# project_1_1.net
KiCad netlist of a schematic drawn in Altium Designer
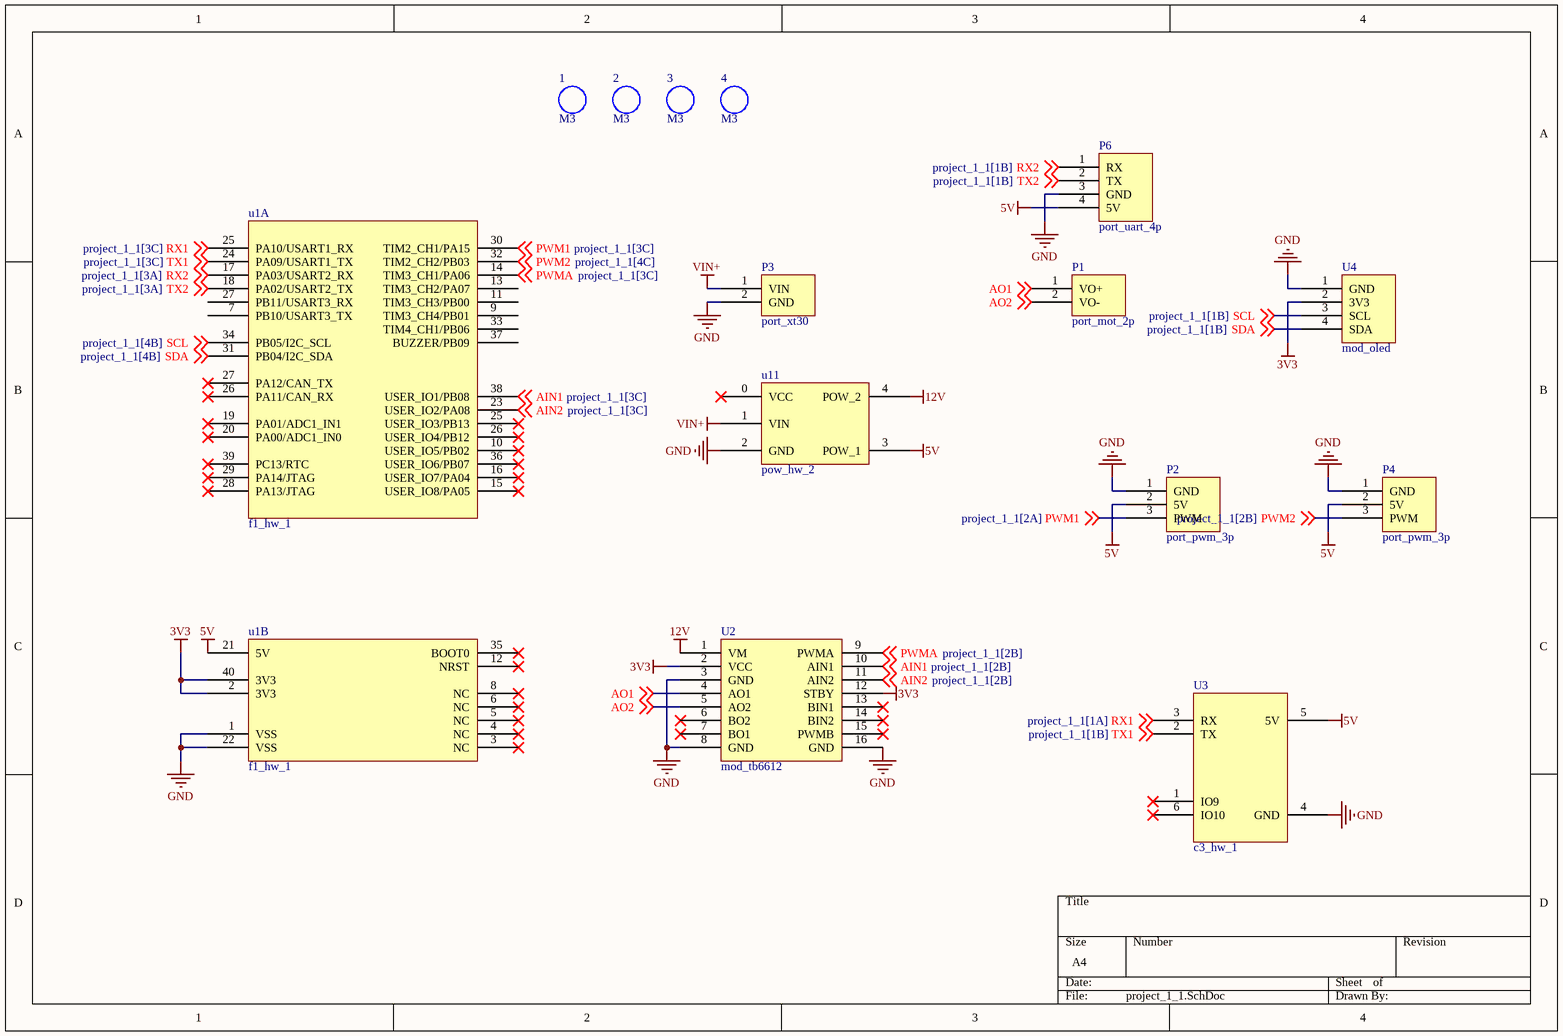
[diagram p0: project_1_1.SchDoc]

(export (version "E")
  (design (tool "Eeschema 10.0.6"))
  (components
    (comp (ref "1")
      (value "M3")
      (footprint "M3 125X200")
      (description "m3铜柱孔")
      (fields (field (name "版权归属") "源创客"))
      (libsource (lib "userLib") (part "prot_m3"))
    )
    (comp (ref "2")
      (value "M3")
      (footprint "M3 125X200")
      (description "m3铜柱孔")
      (fields (field (name "版权归属") "源创客"))
      (libsource (lib "userLib") (part "prot_m3"))
    )
    (comp (ref "3")
      (value "M3")
      (footprint "M3 125X200")
      (description "m3铜柱孔")
      (fields (field (name "版权归属") "源创客"))
      (libsource (lib "userLib") (part "prot_m3"))
    )
    (comp (ref "4")
      (value "M3")
      (footprint "M3 125X200")
      (description "m3铜柱孔")
      (fields (field (name "版权归属") "源创客"))
      (libsource (lib "userLib") (part "prot_m3"))
    )
    (comp (ref "P1")
      (value "port_mot_2p")
      (footprint "XH2.54_2P")
      (description "开环直流电机接口\r\nXH2.54弯排针2p")
      (libsource (lib "userLib") (part "port_mot_2p"))
    )
    (comp (ref "P2")
      (value "port_pwm_3p")
      (footprint "XH2.54_3P")
      (description "舵机接口\r\nXH2.54弯排针3p")
      (libsource (lib "userLib") (part "port_pwm_3p"))
    )
    (comp (ref "P3")
      (value "port_xt30")
      (footprint "MOD_XT30")
      (description "XT30")
      (libsource (lib "userLib") (part "port_xt30"))
    )
    (comp (ref "P4")
      (value "port_pwm_3p")
      (footprint "XH2.54_3P")
      (description "舵机接口\r\nXH2.54弯排针3p")
      (libsource (lib "userLib") (part "port_pwm_3p"))
    )
    (comp (ref "P6")
      (value "port_uart_4p")
      (footprint "XH2.54_4P")
      (description "串口接口/SPP蓝牙模块\r\nXH2.54弯排针4p/4p排母")
      (libsource (lib "userLib") (part "port_uart_4p"))
    )
    (comp (ref "u1")
      (value "f1_hw_1")
      (footprint "f1_hw_1")
      (description "F103C8T6最小系统_1")
      (libsource (lib "userLib") (part "f1_hw_1"))
    )
    (comp (ref "U2")
      (value "mod_tb6612")
      (footprint "MOD_TB6612")
      (description "TB6612模块\r\n8p排母*2")
      (libsource (lib "userLib") (part "mod_tb6612"))
    )
    (comp (ref "U3")
      (value "c3_hw_1")
      (footprint "C3_HW_1")
      (description "ESP32C3蓝牙模块\r\n6p排母")
      (libsource (lib "userLib") (part "c3_hw_1"))
    )
    (comp (ref "U4")
      (value "mod_oled")
      (footprint "mod_oled")
      (description "外购屏幕模块")
      (libsource (lib "userLib") (part "mod_oled"))
    )
    (comp (ref "u11")
      (value "pow_hw_2")
      (footprint "pow_hw_2")
      (description "两路升降压电源模块\r\n6p排母*2")
      (libsource (lib "userLib") (part "pow_hw_2"))
    )
  )
  (nets
    (net (code "1") (name "3V3") (class "Default")
      (node (ref "U2") (pin "12") (pinfunction "STBY_12") (pintype "passive"))
      (node (ref "U2") (pin "2") (pinfunction "VCC_2") (pintype "passive"))
      (node (ref "U4") (pin "2") (pinfunction "3V3_2") (pintype "passive"))
      (node (ref "u1") (pin "2") (pinfunction "3V3_2") (pintype "passive"))
      (node (ref "u1") (pin "40") (pinfunction "3V3_40") (pintype "passive"))
    )
    (net (code "2") (name "5V") (class "Default")
      (node (ref "P2") (pin "2") (pinfunction "5V_2") (pintype "passive"))
      (node (ref "P4") (pin "2") (pinfunction "5V_2") (pintype "passive"))
      (node (ref "P6") (pin "4") (pinfunction "5V_4") (pintype "passive"))
      (node (ref "U3") (pin "5") (pinfunction "5V_5") (pintype "passive"))
      (node (ref "u1") (pin "21") (pinfunction "5V_21") (pintype "passive"))
      (node (ref "u11") (pin "3") (pinfunction "POW_1_3") (pintype "passive"))
    )
    (net (code "3") (name "12V") (class "Default")
      (node (ref "U2") (pin "1") (pinfunction "VM_1") (pintype "passive"))
      (node (ref "u11") (pin "4") (pinfunction "POW_2_4") (pintype "passive"))
    )
    (net (code "4") (name "AIN1") (class "Default")
      (node (ref "U2") (pin "10") (pinfunction "AIN1_10") (pintype "passive"))
      (node (ref "u1") (pin "38") (pinfunction "USER_IO1/PB08_38") (pintype "passive"))
    )
    (net (code "5") (name "AIN2") (class "Default")
      (node (ref "U2") (pin "11") (pinfunction "AIN2_11") (pintype "passive"))
      (node (ref "u1") (pin "23") (pinfunction "USER_IO2/PA08_23") (pintype "passive"))
    )
    (net (code "6") (name "AO1") (class "Default")
      (node (ref "P1") (pin "1") (pinfunction "VO+_1") (pintype "passive"))
      (node (ref "U2") (pin "4") (pinfunction "AO1_4") (pintype "passive"))
    )
    (net (code "7") (name "AO2") (class "Default")
      (node (ref "P1") (pin "2") (pinfunction "VO-_2") (pintype "passive"))
      (node (ref "U2") (pin "5") (pinfunction "AO2_5") (pintype "passive"))
    )
    (net (code "8") (name "GND") (class "Default")
      (node (ref "P2") (pin "1") (pinfunction "GND_1") (pintype "passive"))
      (node (ref "P3") (pin "2") (pinfunction "GND_2") (pintype "passive"))
      (node (ref "P4") (pin "1") (pinfunction "GND_1") (pintype "passive"))
      (node (ref "P6") (pin "3") (pinfunction "GND_3") (pintype "passive"))
      (node (ref "U2") (pin "16") (pinfunction "GND_16") (pintype "passive"))
      (node (ref "U2") (pin "3") (pinfunction "GND_3") (pintype "passive"))
      (node (ref "U2") (pin "8") (pinfunction "GND_8") (pintype "passive"))
      (node (ref "U3") (pin "4") (pinfunction "GND_4") (pintype "passive"))
      (node (ref "U4") (pin "1") (pinfunction "GND_1") (pintype "passive"))
      (node (ref "u1") (pin "1") (pinfunction "VSS_1") (pintype "passive"))
      (node (ref "u1") (pin "22") (pinfunction "VSS_22") (pintype "passive"))
      (node (ref "u11") (pin "2") (pinfunction "GND_2") (pintype "passive"))
    )
    (net (code "9") (name "PWM1") (class "Default")
      (node (ref "P2") (pin "3") (pinfunction "PWM_3") (pintype "passive"))
      (node (ref "u1") (pin "30") (pinfunction "TIM2_CH1/PA15_30") (pintype "passive"))
    )
    (net (code "10") (name "PWM2") (class "Default")
      (node (ref "P4") (pin "3") (pinfunction "PWM_3") (pintype "passive"))
      (node (ref "u1") (pin "32") (pinfunction "TIM2_CH2/PB03_32") (pintype "passive"))
    )
    (net (code "11") (name "PWMA") (class "Default")
      (node (ref "U2") (pin "9") (pinfunction "PWMA_9") (pintype "passive"))
      (node (ref "u1") (pin "14") (pinfunction "TIM3_CH1/PA06_14") (pintype "passive"))
    )
    (net (code "12") (name "RX1") (class "Default")
      (node (ref "U3") (pin "3") (pinfunction "RX_3") (pintype "passive"))
      (node (ref "u1") (pin "25") (pinfunction "PA10/USART1_RX_25") (pintype "passive"))
    )
    (net (code "13") (name "RX2") (class "Default")
      (node (ref "P6") (pin "1") (pinfunction "RX_1") (pintype "passive"))
      (node (ref "u1") (pin "17") (pinfunction "PA03/USART2_RX_17") (pintype "passive"))
    )
    (net (code "14") (name "SCL") (class "Default")
      (node (ref "U4") (pin "3") (pinfunction "SCL_3") (pintype "passive"))
      (node (ref "u1") (pin "34") (pinfunction "PB05/I2C_SCL_34") (pintype "passive"))
    )
    (net (code "15") (name "SDA") (class "Default")
      (node (ref "U4") (pin "4") (pinfunction "SDA_4") (pintype "passive"))
      (node (ref "u1") (pin "31") (pinfunction "PB04/I2C_SDA_31") (pintype "passive"))
    )
    (net (code "16") (name "TX1") (class "Default")
      (node (ref "U3") (pin "2") (pinfunction "TX_2") (pintype "passive"))
      (node (ref "u1") (pin "24") (pinfunction "PA09/USART1_TX_24") (pintype "passive"))
    )
    (net (code "17") (name "TX2") (class "Default")
      (node (ref "P6") (pin "2") (pinfunction "TX_2") (pintype "passive"))
      (node (ref "u1") (pin "18") (pinfunction "PA02/USART2_TX_18") (pintype "passive"))
    )
    (net (code "18") (name "VIN+") (class "Default")
      (node (ref "P3") (pin "1") (pinfunction "VIN_1") (pintype "passive"))
      (node (ref "u11") (pin "1") (pinfunction "VIN_1") (pintype "passive"))
    )
    (net (code "19") (name "unconnected-(U2-BIN1-Pad13)") (class "Default")
      (node (ref "U2") (pin "13") (pinfunction "BIN1_13") (pintype "passive+no_connect"))
    )
    (net (code "20") (name "unconnected-(U2-BIN2-Pad14)") (class "Default")
      (node (ref "U2") (pin "14") (pinfunction "BIN2_14") (pintype "passive+no_connect"))
    )
    (net (code "21") (name "unconnected-(U2-BO1-Pad7)") (class "Default")
      (node (ref "U2") (pin "7") (pinfunction "BO1_7") (pintype "passive+no_connect"))
    )
    (net (code "22") (name "unconnected-(U2-BO2-Pad6)") (class "Default")
      (node (ref "U2") (pin "6") (pinfunction "BO2_6") (pintype "passive+no_connect"))
    )
    (net (code "23") (name "unconnected-(U2-PWMB-Pad15)") (class "Default")
      (node (ref "U2") (pin "15") (pinfunction "PWMB_15") (pintype "passive+no_connect"))
    )
    (net (code "24") (name "unconnected-(U3-IO9-Pad1)") (class "Default")
      (node (ref "U3") (pin "1") (pinfunction "IO9_1") (pintype "passive+no_connect"))
    )
    (net (code "25") (name "unconnected-(U3-IO10-Pad6)") (class "Default")
      (node (ref "U3") (pin "6") (pinfunction "IO10_6") (pintype "passive+no_connect"))
    )
    (net (code "26") (name "unconnected-(u1A-BUZZER{slash}PB09-Pad37)") (class "Default")
      (node (ref "u1") (pin "37") (pinfunction "BUZZER/PB09_37") (pintype "passive"))
    )
    (net (code "27") (name "unconnected-(u1A-PA00{slash}ADC1_IN0-Pad20)") (class "Default")
      (node (ref "u1") (pin "20") (pinfunction "PA00/ADC1_IN0_20") (pintype "passive+no_connect"))
    )
    (net (code "28") (name "unconnected-(u1A-PA01{slash}ADC1_IN1-Pad19)") (class "Default")
      (node (ref "u1") (pin "19") (pinfunction "PA01/ADC1_IN1_19") (pintype "passive+no_connect"))
    )
    (net (code "29") (name "unconnected-(u1A-PA11{slash}CAN_RX-Pad26)") (class "Default")
      (node (ref "u1") (pin "26") (pinfunction "PA11/CAN_RX_26") (pintype "passive+no_connect"))
    )
    (net (code "30") (name "unconnected-(u1A-PA12{slash}CAN_TX-Pad27)") (class "Default")
      (node (ref "u1") (pin "27") (pinfunction "PA12/CAN_TX_27") (pintype "passive+no_connect"))
    )
    (net (code "31") (name "unconnected-(u1A-PA13{slash}JTAG-Pad28)") (class "Default")
      (node (ref "u1") (pin "28") (pinfunction "PA13/JTAG_28") (pintype "passive+no_connect"))
    )
    (net (code "32") (name "unconnected-(u1A-PA14{slash}JTAG-Pad29)") (class "Default")
      (node (ref "u1") (pin "29") (pinfunction "PA14/JTAG_29") (pintype "passive+no_connect"))
    )
    (net (code "33") (name "unconnected-(u1A-PB10{slash}USART3_TX-Pad7)") (class "Default")
      (node (ref "u1") (pin "7") (pinfunction "PB10/USART3_TX_7") (pintype "passive"))
    )
    (net (code "34") (name "unconnected-(u1A-PB11{slash}USART3_RX-Pad27)") (class "Default")
      (node (ref "u1") (pin "27") (pinfunction "PB11/USART3_RX_27") (pintype "passive"))
    )
    (net (code "35") (name "unconnected-(u1A-PC13{slash}RTC-Pad39)") (class "Default")
      (node (ref "u1") (pin "39") (pinfunction "PC13/RTC_39") (pintype "passive+no_connect"))
    )
    (net (code "36") (name "unconnected-(u1A-TIM3_CH2{slash}PA07-Pad13)") (class "Default")
      (node (ref "u1") (pin "13") (pinfunction "TIM3_CH2/PA07_13") (pintype "passive"))
    )
    (net (code "37") (name "unconnected-(u1A-TIM3_CH3{slash}PB00-Pad11)") (class "Default")
      (node (ref "u1") (pin "11") (pinfunction "TIM3_CH3/PB00_11") (pintype "passive"))
    )
    (net (code "38") (name "unconnected-(u1A-TIM3_CH4{slash}PB01-Pad9)") (class "Default")
      (node (ref "u1") (pin "9") (pinfunction "TIM3_CH4/PB01_9") (pintype "passive"))
    )
    (net (code "39") (name "unconnected-(u1A-TIM4_CH1{slash}PB06-Pad33)") (class "Default")
      (node (ref "u1") (pin "33") (pinfunction "TIM4_CH1/PB06_33") (pintype "passive"))
    )
    (net (code "40") (name "unconnected-(u1A-USER_IO3{slash}PB13-Pad25)") (class "Default")
      (node (ref "u1") (pin "25") (pinfunction "USER_IO3/PB13_25") (pintype "passive+no_connect"))
    )
    (net (code "41") (name "unconnected-(u1A-USER_IO4{slash}PB12-Pad26)") (class "Default")
      (node (ref "u1") (pin "26") (pinfunction "USER_IO4/PB12_26") (pintype "passive+no_connect"))
    )
    (net (code "42") (name "unconnected-(u1A-USER_IO5{slash}PB02-Pad10)") (class "Default")
      (node (ref "u1") (pin "10") (pinfunction "USER_IO5/PB02_10") (pintype "passive+no_connect"))
    )
    (net (code "43") (name "unconnected-(u1A-USER_IO6{slash}PB07-Pad36)") (class "Default")
      (node (ref "u1") (pin "36") (pinfunction "USER_IO6/PB07_36") (pintype "passive+no_connect"))
    )
    (net (code "44") (name "unconnected-(u1A-USER_IO7{slash}PA04-Pad16)") (class "Default")
      (node (ref "u1") (pin "16") (pinfunction "USER_IO7/PA04_16") (pintype "passive+no_connect"))
    )
    (net (code "45") (name "unconnected-(u1A-USER_IO8{slash}PA05-Pad15)") (class "Default")
      (node (ref "u1") (pin "15") (pinfunction "USER_IO8/PA05_15") (pintype "passive+no_connect"))
    )
    (net (code "46") (name "unconnected-(u1B-BOOT0-Pad35)") (class "Default")
      (node (ref "u1") (pin "35") (pinfunction "BOOT0_35") (pintype "passive+no_connect"))
    )
    (net (code "47") (name "unconnected-(u1B-NC-Pad3)") (class "Default")
      (node (ref "u1") (pin "3") (pinfunction "NC_3") (pintype "passive+no_connect"))
    )
    (net (code "48") (name "unconnected-(u1B-NC-Pad4)") (class "Default")
      (node (ref "u1") (pin "4") (pinfunction "NC_4") (pintype "passive+no_connect"))
    )
    (net (code "49") (name "unconnected-(u1B-NC-Pad5)") (class "Default")
      (node (ref "u1") (pin "5") (pinfunction "NC_5") (pintype "passive+no_connect"))
    )
    (net (code "50") (name "unconnected-(u1B-NC-Pad6)") (class "Default")
      (node (ref "u1") (pin "6") (pinfunction "NC_6") (pintype "passive+no_connect"))
    )
    (net (code "51") (name "unconnected-(u1B-NC-Pad8)") (class "Default")
      (node (ref "u1") (pin "8") (pinfunction "NC_8") (pintype "passive+no_connect"))
    )
    (net (code "52") (name "unconnected-(u1B-NRST-Pad12)") (class "Default")
      (node (ref "u1") (pin "12") (pinfunction "NRST_12") (pintype "passive+no_connect"))
    )
    (net (code "53") (name "unconnected-(u11-VCC-Pad0)") (class "Default")
      (node (ref "u11") (pin "0") (pinfunction "VCC_0") (pintype "passive+no_connect"))
    )
  )
)
